# L_26R_Overcurrent_Analog.net
KiCad netlist of a schematic drawn in EAGLE
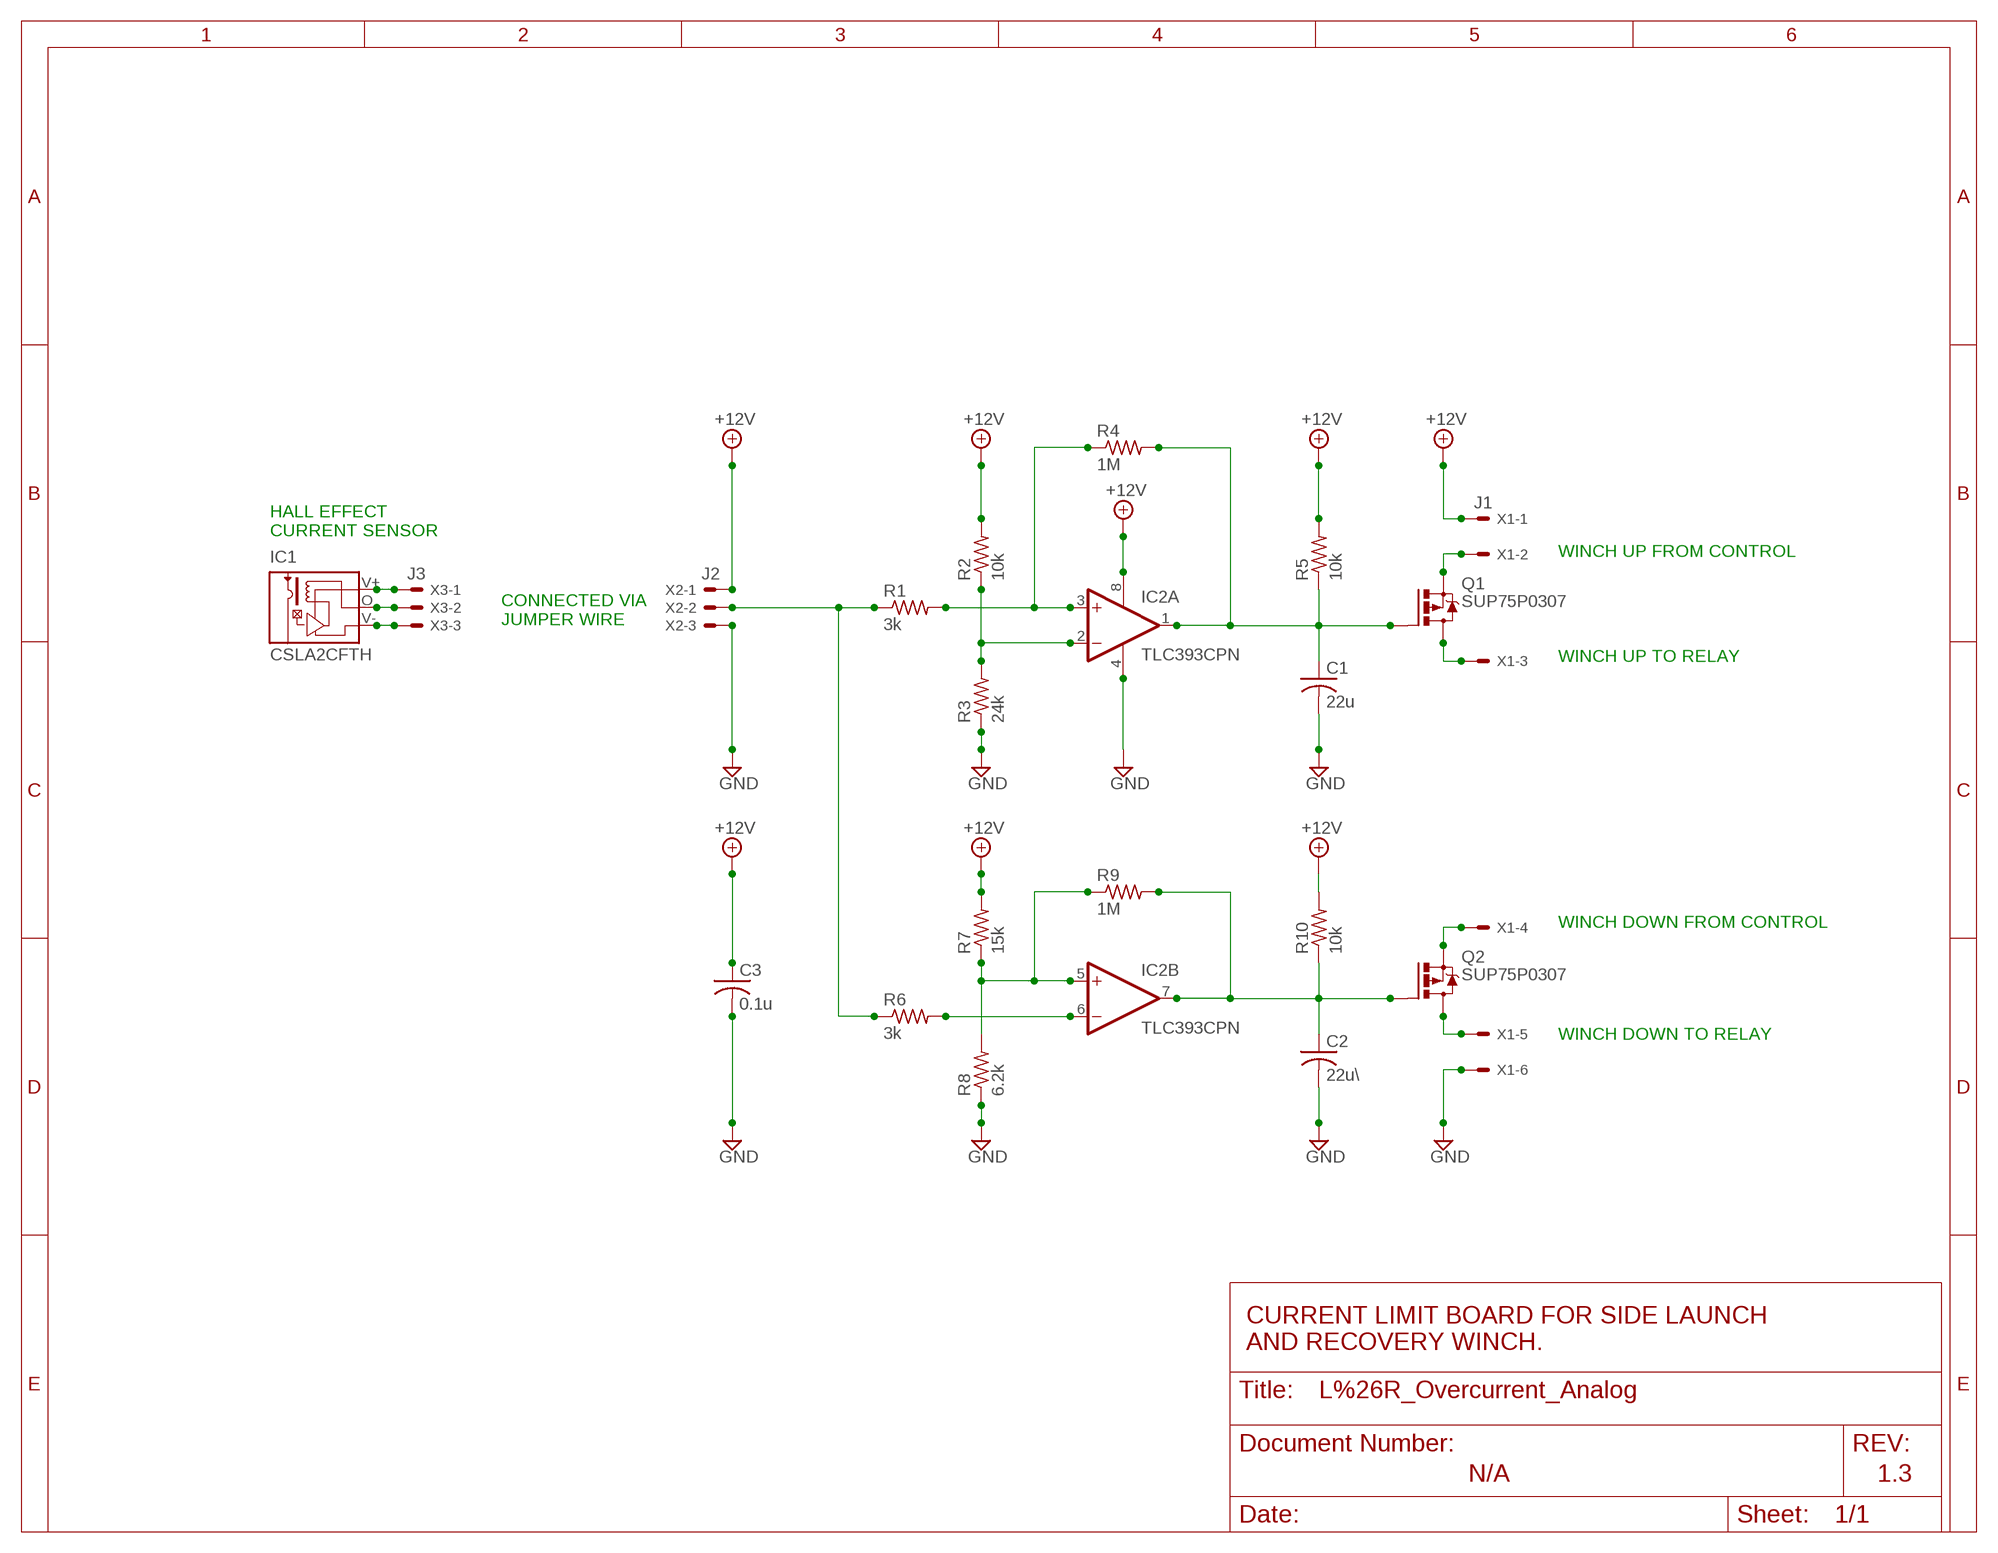
[diagram p0: schematic, sheet 1]

(export (version "E")
  (design (tool "Eeschema 10.0.6"))
  (components
    (comp (ref "C1")
      (value "22u")
      (footprint "eagle-import:C025-050X050")
      (libsource (lib "eagle-import") (part "CAPACITOR-US025-050X050"))
    )
    (comp (ref "C2")
      (value "22u\\")
      (footprint "eagle-import:C025-050X050")
      (libsource (lib "eagle-import") (part "CAPACITOR-US025-050X050"))
    )
    (comp (ref "C3")
      (value "0.1u")
      (footprint "eagle-import:C050-024X044")
      (libsource (lib "eagle-import") (part "CAPACITOR-US"))
    )
    (comp (ref "IC1")
      (value "CSLA2CFTH")
      (footprint "eagle-import:CSLA2CF")
      (libsource (lib "eagle-import") (part "CSLA2CFTH"))
    )
    (comp (ref "IC2")
      (value "TLC393CPN")
      (footprint "eagle-import:DIL08")
      (libsource (lib "eagle-import") (part "TLC393CPN"))
    )
    (comp (ref "Q1")
      (value "SUP75P0307")
      (footprint "eagle-import:TO220BV")
      (libsource (lib "eagle-import") (part "SUP75P0307"))
    )
    (comp (ref "Q2")
      (value "SUP75P0307")
      (footprint "eagle-import:TO220BV")
      (libsource (lib "eagle-import") (part "SUP75P0307"))
    )
    (comp (ref "R1")
      (value "3k")
      (footprint "eagle-import:0204_7")
      (libsource (lib "eagle-import") (part "RESISTOR-US0204/7"))
    )
    (comp (ref "R2")
      (value "10k")
      (footprint "eagle-import:0204_7")
      (libsource (lib "eagle-import") (part "RESISTOR-US0204/7"))
    )
    (comp (ref "R3")
      (value "24k")
      (footprint "eagle-import:0204_7")
      (libsource (lib "eagle-import") (part "RESISTOR-US0204/7"))
    )
    (comp (ref "R4")
      (value "1M")
      (footprint "eagle-import:0204_7")
      (libsource (lib "eagle-import") (part "RESISTOR-US0204/7"))
    )
    (comp (ref "R5")
      (value "10k")
      (footprint "eagle-import:0204_7")
      (libsource (lib "eagle-import") (part "RESISTOR-US0204/7"))
    )
    (comp (ref "R6")
      (value "3k")
      (footprint "eagle-import:0204_7")
      (libsource (lib "eagle-import") (part "RESISTOR-US0204/7"))
    )
    (comp (ref "R7")
      (value "15k")
      (footprint "eagle-import:0204_7")
      (libsource (lib "eagle-import") (part "RESISTOR-US0204/7"))
    )
    (comp (ref "R8")
      (value "6.2k")
      (footprint "eagle-import:0204_7")
      (libsource (lib "eagle-import") (part "RESISTOR-US0204/7"))
    )
    (comp (ref "R9")
      (value "1M")
      (footprint "eagle-import:0204_7")
      (libsource (lib "eagle-import") (part "RESISTOR-US0204/7"))
    )
    (comp (ref "R10")
      (value "10k")
      (footprint "eagle-import:0204_7")
      (libsource (lib "eagle-import") (part "RESISTOR-US0204/7"))
    )
    (comp (ref "X1")
      (value "J1")
      (footprint "eagle-import:22-23-2061")
      (fields (field (name "MF") "MOLEX") (field (name "MPN") "22-23-2061"))
      (libsource (lib "eagle-import") (part "6PIN_HEADER"))
    )
    (comp (ref "X2")
      (value "J2")
      (footprint "eagle-import:22-23-2031")
      (fields (field (name "MF") "MOLEX") (field (name "MPN") "22-23-2031"))
      (libsource (lib "eagle-import") (part "22-23-2031"))
    )
    (comp (ref "X3")
      (value "J3")
      (footprint "eagle-import:22-23-2031")
      (fields (field (name "MF") "MOLEX") (field (name "MPN") "22-23-2031"))
      (libsource (lib "eagle-import") (part "22-23-2031"))
    )
  )
  (nets
    (net (code "1") (name "+12V") (class "Default")
      (node (ref "C3") (pin "1") (pinfunction "1_1") (pintype "passive"))
      (node (ref "IC2") (pin "8") (pinfunction "V+_8") (pintype "power_in"))
      (node (ref "R10") (pin "2") (pinfunction "2_2") (pintype "passive"))
      (node (ref "R2") (pin "2") (pinfunction "2_2") (pintype "passive"))
      (node (ref "R5") (pin "2") (pinfunction "2_2") (pintype "passive"))
      (node (ref "R7") (pin "2") (pinfunction "2_2") (pintype "passive"))
      (node (ref "X1") (pin "1") (pinfunction "S_1") (pintype "passive"))
      (node (ref "X2") (pin "1") (pinfunction "S_1") (pintype "passive"))
    )
    (net (code "2") (name "GND") (class "Default")
      (node (ref "C1") (pin "2") (pinfunction "2_2") (pintype "passive"))
      (node (ref "C2") (pin "2") (pinfunction "2_2") (pintype "passive"))
      (node (ref "C3") (pin "2") (pinfunction "2_2") (pintype "passive"))
      (node (ref "IC2") (pin "4") (pinfunction "V-_4") (pintype "power_in"))
      (node (ref "R3") (pin "1") (pinfunction "1_1") (pintype "passive"))
      (node (ref "R8") (pin "1") (pinfunction "1_1") (pintype "passive"))
      (node (ref "X1") (pin "6") (pinfunction "S_6") (pintype "passive"))
      (node (ref "X2") (pin "3") (pinfunction "S_3") (pintype "passive"))
    )
    (net (code "3") (name "Net-(IC1-M)") (class "Default")
      (node (ref "IC1") (pin "O") (pinfunction "M_O") (pintype "output"))
      (node (ref "X3") (pin "2") (pinfunction "S_2") (pintype "passive"))
    )
    (net (code "4") (name "Net-(IC2A-+IN)") (class "Default")
      (node (ref "IC2") (pin "3") (pinfunction "+IN_3") (pintype "input"))
      (node (ref "R1") (pin "2") (pinfunction "2_2") (pintype "passive"))
      (node (ref "R4") (pin "1") (pinfunction "1_1") (pintype "passive"))
    )
    (net (code "5") (name "Net-(IC2A--IN)") (class "Default")
      (node (ref "IC2") (pin "2") (pinfunction "-IN_2") (pintype "input"))
      (node (ref "R2") (pin "1") (pinfunction "1_1") (pintype "passive"))
      (node (ref "R3") (pin "2") (pinfunction "2_2") (pintype "passive"))
    )
    (net (code "6") (name "Net-(IC2A-OUT)") (class "Default")
      (node (ref "C1") (pin "1") (pinfunction "1_1") (pintype "passive"))
      (node (ref "IC2") (pin "1") (pinfunction "OUT_1") (pintype "output"))
      (node (ref "Q1") (pin "G") (pinfunction "G_G") (pintype "passive"))
      (node (ref "R4") (pin "2") (pinfunction "2_2") (pintype "passive"))
      (node (ref "R5") (pin "1") (pinfunction "1_1") (pintype "passive"))
    )
    (net (code "7") (name "Net-(IC2B-+IN)") (class "Default")
      (node (ref "IC2") (pin "5") (pinfunction "+IN_5") (pintype "input"))
      (node (ref "R7") (pin "1") (pinfunction "1_1") (pintype "passive"))
      (node (ref "R8") (pin "2") (pinfunction "2_2") (pintype "passive"))
      (node (ref "R9") (pin "1") (pinfunction "1_1") (pintype "passive"))
    )
    (net (code "8") (name "Net-(IC2B--IN)") (class "Default")
      (node (ref "IC2") (pin "6") (pinfunction "-IN_6") (pintype "input"))
      (node (ref "R6") (pin "2") (pinfunction "2_2") (pintype "passive"))
    )
    (net (code "9") (name "Net-(IC2B-OUT)") (class "Default")
      (node (ref "C2") (pin "1") (pinfunction "1_1") (pintype "passive"))
      (node (ref "IC2") (pin "7") (pinfunction "OUT_7") (pintype "output"))
      (node (ref "Q2") (pin "G") (pinfunction "G_G") (pintype "passive"))
      (node (ref "R10") (pin "1") (pinfunction "1_1") (pintype "passive"))
      (node (ref "R9") (pin "2") (pinfunction "2_2") (pintype "passive"))
    )
    (net (code "10") (name "Net-(X1B-S)") (class "Default")
      (node (ref "Q1") (pin "S") (pinfunction "S_S") (pintype "passive"))
      (node (ref "X1") (pin "2") (pinfunction "S_2") (pintype "passive"))
    )
    (net (code "11") (name "Net-(X1C-S)") (class "Default")
      (node (ref "Q1") (pin "D") (pinfunction "D_D") (pintype "passive"))
      (node (ref "X1") (pin "3") (pinfunction "S_3") (pintype "passive"))
    )
    (net (code "12") (name "Net-(X1D-S)") (class "Default")
      (node (ref "Q2") (pin "S") (pinfunction "S_S") (pintype "passive"))
      (node (ref "X1") (pin "4") (pinfunction "S_4") (pintype "passive"))
    )
    (net (code "13") (name "Net-(X1E-S)") (class "Default")
      (node (ref "Q2") (pin "D") (pinfunction "D_D") (pintype "passive"))
      (node (ref "X1") (pin "5") (pinfunction "S_5") (pintype "passive"))
    )
    (net (code "14") (name "Net-(X2B-S)") (class "Default")
      (node (ref "R1") (pin "1") (pinfunction "1_1") (pintype "passive"))
      (node (ref "R6") (pin "1") (pinfunction "1_1") (pintype "passive"))
      (node (ref "X2") (pin "2") (pinfunction "S_2") (pintype "passive"))
    )
    (net (code "15") (name "Net-(X3A-S)") (class "Default")
      (node (ref "IC1") (pin "V+") (pinfunction "V+_V+") (pintype "input"))
      (node (ref "X3") (pin "1") (pinfunction "S_1") (pintype "passive"))
    )
    (net (code "16") (name "Net-(X3C-S)") (class "Default")
      (node (ref "IC1") (pin "V-") (pinfunction "V-_V-") (pintype "input"))
      (node (ref "X3") (pin "3") (pinfunction "S_3") (pintype "passive"))
    )
  )
)
